# SWR.net
KiCad netlist of a schematic drawn in Altium Designer
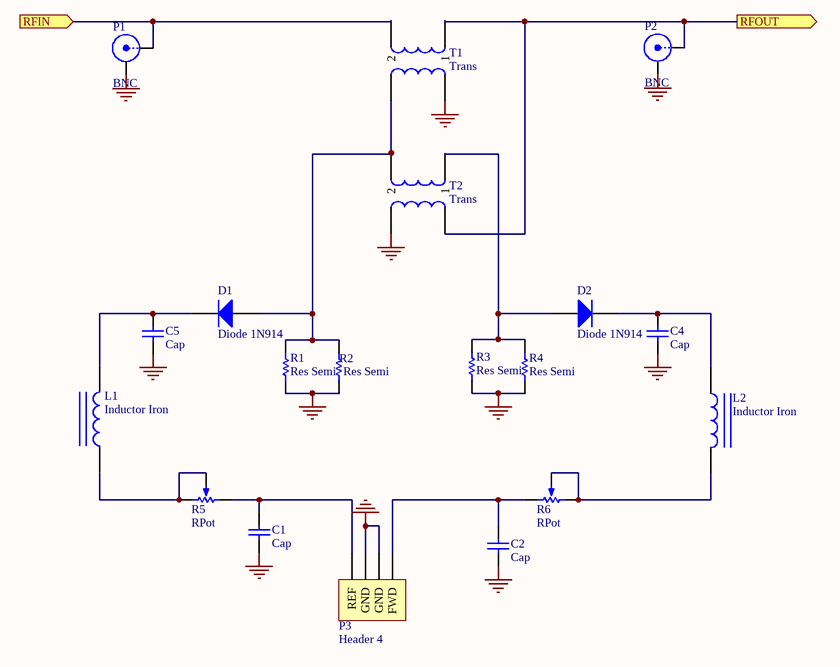
[diagram p0: SWR.SchDoc]

(export (version "E")
  (design (tool "Eeschema 10.0.6"))
  (components
    (comp (ref "C1")
      (value "Cap")
      (footprint "RAD-0.3")
      (description "Capacitor")
      (fields (field (name "PUBLISHER") "Altium Limited"))
      (libsource (lib "Miscellaneous Devices") (part "Cap"))
    )
    (comp (ref "C2")
      (value "Cap")
      (footprint "RAD-0.3")
      (description "Capacitor")
      (fields (field (name "PUBLISHER") "Altium Limited"))
      (libsource (lib "Miscellaneous Devices") (part "Cap"))
    )
    (comp (ref "C4")
      (value "Cap")
      (footprint "RAD-0.3")
      (description "Capacitor")
      (fields (field (name "PUBLISHER") "Altium Limited"))
      (libsource (lib "Miscellaneous Devices") (part "Cap"))
    )
    (comp (ref "C5")
      (value "Cap")
      (footprint "RAD-0.3")
      (description "Capacitor")
      (fields (field (name "PUBLISHER") "Altium Limited"))
      (libsource (lib "Miscellaneous Devices") (part "Cap"))
    )
    (comp (ref "D1")
      (value "Diode 1N914")
      (footprint "DIO7.1-3.9x1.9")
      (description "High Conductance Fast Diode")
      (fields (field (name "PUBLISHER") "Altium Limited"))
      (libsource (lib "Miscellaneous Devices") (part "Diode 1N914"))
    )
    (comp (ref "D2")
      (value "Diode 1N914")
      (footprint "DIO7.1-3.9x1.9")
      (description "High Conductance Fast Diode")
      (fields (field (name "PUBLISHER") "Altium Limited"))
      (libsource (lib "Miscellaneous Devices") (part "Diode 1N914"))
    )
    (comp (ref "L1")
      (value "Inductor Iron")
      (footprint "AXIAL-0.3")
      (description "Magnetic-Core Inductor")
      (fields (field (name "PUBLISHER") "Altium Limited"))
      (libsource (lib "Miscellaneous Devices") (part "Inductor Iron"))
    )
    (comp (ref "L2")
      (value "Inductor Iron")
      (footprint "AXIAL-0.3")
      (description "Magnetic-Core Inductor")
      (fields (field (name "PUBLISHER") "Altium Limited"))
      (libsource (lib "Miscellaneous Devices") (part "Inductor Iron"))
    )
    (comp (ref "P1")
      (value "BNC")
      (footprint "BNC_RA CON")
      (description "BNC Elbow Connector")
      (fields (field (name "PUBLISHER") "Altium Limited"))
      (libsource (lib "Miscellaneous Connectors") (part "BNC"))
    )
    (comp (ref "P2")
      (value "BNC")
      (footprint "BNC_RA CON")
      (description "BNC Elbow Connector")
      (fields (field (name "PUBLISHER") "Altium Limited"))
      (libsource (lib "Miscellaneous Connectors") (part "BNC"))
    )
    (comp (ref "P3")
      (value "Header 4")
      (footprint "HDR1X4")
      (description "Header, 4-Pin")
      (fields (field (name "PUBLISHER") "Altium Limited"))
      (libsource (lib "Miscellaneous Connectors") (part "Header 4"))
    )
    (comp (ref "R1")
      (value "Res Semi")
      (footprint "AXIAL-0.5")
      (description "Semiconductor Resistor")
      (fields (field (name "PUBLISHER") "Altium Limited"))
      (libsource (lib "Miscellaneous Devices") (part "Res Semi"))
    )
    (comp (ref "R2")
      (value "Res Semi")
      (footprint "AXIAL-0.5")
      (description "Semiconductor Resistor")
      (fields (field (name "PUBLISHER") "Altium Limited"))
      (libsource (lib "Miscellaneous Devices") (part "Res Semi"))
    )
    (comp (ref "R3")
      (value "Res Semi")
      (footprint "AXIAL-0.5")
      (description "Semiconductor Resistor")
      (fields (field (name "PUBLISHER") "Altium Limited"))
      (libsource (lib "Miscellaneous Devices") (part "Res Semi"))
    )
    (comp (ref "R4")
      (value "Res Semi")
      (footprint "AXIAL-0.5")
      (description "Semiconductor Resistor")
      (fields (field (name "PUBLISHER") "Altium Limited"))
      (libsource (lib "Miscellaneous Devices") (part "Res Semi"))
    )
    (comp (ref "R5")
      (value "RPot")
      (footprint "VR5")
      (description "Potentiometer")
      (fields (field (name "PUBLISHER") "Altium Limited"))
      (libsource (lib "Miscellaneous Devices") (part "RPot"))
    )
    (comp (ref "R6")
      (value "RPot")
      (footprint "VR5")
      (description "Potentiometer")
      (fields (field (name "PUBLISHER") "Altium Limited"))
      (libsource (lib "Miscellaneous Devices") (part "RPot"))
    )
    (comp (ref "T1")
      (value "Trans")
      (footprint "TRANS")
      (description "Transformer")
      (fields (field (name "PUBLISHER") "Altium Limited"))
      (libsource (lib "Miscellaneous Devices") (part "Trans"))
    )
    (comp (ref "T2")
      (value "Trans")
      (footprint "TRANS")
      (description "Transformer")
      (fields (field (name "PUBLISHER") "Altium Limited"))
      (libsource (lib "Miscellaneous Devices") (part "Trans"))
    )
  )
  (nets
    (net (code "1") (name "/RFIN") (class "Default")
      (node (ref "P1") (pin "1") (pinfunction "X_1") (pintype "passive"))
      (node (ref "T1") (pin "2") (pinfunction "2_2") (pintype "passive"))
    )
    (net (code "2") (name "/RFOUT") (class "Default")
      (node (ref "P2") (pin "1") (pinfunction "X_1") (pintype "passive"))
      (node (ref "T1") (pin "1") (pinfunction "1_1") (pintype "passive"))
      (node (ref "T2") (pin "3") (pinfunction "3_3") (pintype "passive"))
    )
    (net (code "3") (name "GND") (class "Default")
      (node (ref "C1") (pin "1") (pinfunction "1_1") (pintype "passive"))
      (node (ref "C2") (pin "1") (pinfunction "1_1") (pintype "passive"))
      (node (ref "C4") (pin "1") (pinfunction "1_1") (pintype "passive"))
      (node (ref "C5") (pin "1") (pinfunction "1_1") (pintype "passive"))
      (node (ref "P1") (pin "2") (pinfunction "Y_2") (pintype "passive"))
      (node (ref "P2") (pin "2") (pinfunction "Y_2") (pintype "passive"))
      (node (ref "P3") (pin "2") (pinfunction "GND_2") (pintype "passive"))
      (node (ref "P3") (pin "3") (pinfunction "GND_3") (pintype "passive"))
      (node (ref "R1") (pin "1") (pinfunction "1_1") (pintype "passive"))
      (node (ref "R2") (pin "1") (pinfunction "1_1") (pintype "passive"))
      (node (ref "R3") (pin "1") (pinfunction "1_1") (pintype "passive"))
      (node (ref "R4") (pin "1") (pinfunction "1_1") (pintype "passive"))
      (node (ref "T1") (pin "3") (pinfunction "3_3") (pintype "passive"))
      (node (ref "T2") (pin "4") (pinfunction "4_4") (pintype "passive"))
    )
    (net (code "4") (name "Net-(D1-A)") (class "Default")
      (node (ref "D1") (pin "1") (pinfunction "A_1") (pintype "passive"))
      (node (ref "R1") (pin "2") (pinfunction "2_2") (pintype "passive"))
      (node (ref "R2") (pin "2") (pinfunction "2_2") (pintype "passive"))
      (node (ref "T1") (pin "4") (pinfunction "4_4") (pintype "passive"))
      (node (ref "T2") (pin "2") (pinfunction "2_2") (pintype "passive"))
    )
    (net (code "5") (name "Net-(D1-K)") (class "Default")
      (node (ref "C5") (pin "2") (pinfunction "2_2") (pintype "passive"))
      (node (ref "D1") (pin "2") (pinfunction "K_2") (pintype "passive"))
      (node (ref "L1") (pin "2") (pinfunction "2_2") (pintype "passive"))
    )
    (net (code "6") (name "Net-(D2-A)") (class "Default")
      (node (ref "D2") (pin "1") (pinfunction "A_1") (pintype "passive"))
      (node (ref "R3") (pin "2") (pinfunction "2_2") (pintype "passive"))
      (node (ref "R4") (pin "2") (pinfunction "2_2") (pintype "passive"))
      (node (ref "T2") (pin "1") (pinfunction "1_1") (pintype "passive"))
    )
    (net (code "7") (name "Net-(D2-K)") (class "Default")
      (node (ref "C4") (pin "2") (pinfunction "2_2") (pintype "passive"))
      (node (ref "D2") (pin "2") (pinfunction "K_2") (pintype "passive"))
      (node (ref "L2") (pin "1") (pinfunction "1_1") (pintype "passive"))
    )
    (net (code "8") (name "Net-(P3-FWD)") (class "Default")
      (node (ref "C2") (pin "2") (pinfunction "2_2") (pintype "passive"))
      (node (ref "P3") (pin "1") (pinfunction "FWD_1") (pintype "passive"))
      (node (ref "R6") (pin "2") (pinfunction "BOT_2") (pintype "passive"))
    )
    (net (code "9") (name "Net-(P3-REF)") (class "Default")
      (node (ref "C1") (pin "2") (pinfunction "2_2") (pintype "passive"))
      (node (ref "P3") (pin "4") (pinfunction "REF_4") (pintype "passive"))
      (node (ref "R5") (pin "1") (pinfunction "TOP_1") (pintype "passive"))
    )
    (net (code "10") (name "Net-(R5-BOT)") (class "Default")
      (node (ref "L1") (pin "1") (pinfunction "1_1") (pintype "passive"))
      (node (ref "R5") (pin "2") (pinfunction "BOT_2") (pintype "passive"))
      (node (ref "R5") (pin "3") (pinfunction "TAP_3") (pintype "passive"))
    )
    (net (code "11") (name "Net-(R6-TAP)") (class "Default")
      (node (ref "L2") (pin "2") (pinfunction "2_2") (pintype "passive"))
      (node (ref "R6") (pin "1") (pinfunction "TOP_1") (pintype "passive"))
      (node (ref "R6") (pin "3") (pinfunction "TAP_3") (pintype "passive"))
    )
  )
)
